# TMP116.net
KiCad netlist of a schematic drawn in Altium Designer
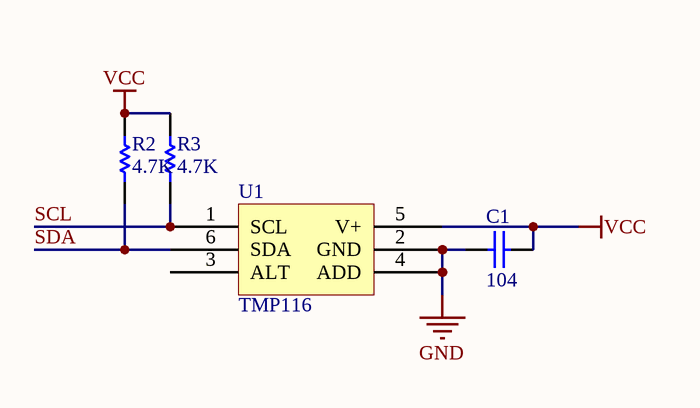
[diagram p0: TMP116.SchDoc]

(export (version "E")
  (design (tool "Eeschema 10.0.6"))
  (components
    (comp (ref "C1")
      (value "104")
      (footprint "0402")
      (description "Capacitor (Semiconductor SIM Model)")
      (fields (field (name "Comment") "Cap Semi") (field (name "PUBLISHER") "Altium Limited"))
      (libsource (lib "Miscellaneous Devices") (part "Cap Semi"))
    )
    (comp (ref "R2")
      (value "4.7K")
      (footprint "0402")
      (description "Resistor")
      (fields (field (name "Comment") "Res1") (field (name "PUBLISHER") "Altium Limited"))
      (libsource (lib "Miscellaneous Devices") (part "Res1"))
    )
    (comp (ref "R3")
      (value "4.7K")
      (footprint "0402")
      (description "Resistor")
      (fields (field (name "Comment") "Res1") (field (name "PUBLISHER") "Altium Limited"))
      (libsource (lib "Miscellaneous Devices") (part "Res1"))
    )
    (comp (ref "U1")
      (value "TMP116")
      (footprint "WSON")
      (fields (field (name "Comment") "Sensor"))
      (libsource (lib "Tank") (part "TMP116"))
    )
  )
  (nets
    (net (code "1") (name "/SCL") (class "Default")
      (node (ref "R3") (pin "2") (pinfunction "2_2") (pintype "passive"))
      (node (ref "U1") (pin "1") (pinfunction "SCL_1") (pintype "passive"))
    )
    (net (code "2") (name "/SDA") (class "Default")
      (node (ref "R2") (pin "2") (pinfunction "2_2") (pintype "passive"))
      (node (ref "U1") (pin "6") (pinfunction "SDA_6") (pintype "passive"))
    )
    (net (code "3") (name "GND") (class "Default")
      (node (ref "C1") (pin "1") (pinfunction "1_1") (pintype "passive"))
      (node (ref "U1") (pin "2") (pinfunction "GND_2") (pintype "passive"))
      (node (ref "U1") (pin "4") (pinfunction "ADD_4") (pintype "passive"))
    )
    (net (code "4") (name "VCC") (class "Default")
      (node (ref "C1") (pin "2") (pinfunction "2_2") (pintype "passive"))
      (node (ref "R2") (pin "1") (pinfunction "1_1") (pintype "passive"))
      (node (ref "R3") (pin "1") (pinfunction "1_1") (pintype "passive"))
      (node (ref "U1") (pin "5") (pinfunction "V+_5") (pintype "passive"))
    )
    (net (code "5") (name "unconnected-(U1-ALT-Pad3)") (class "Default")
      (node (ref "U1") (pin "3") (pinfunction "ALT_3") (pintype "passive"))
    )
  )
)
